# Torent_Module.net
KiCad netlist of a schematic drawn in EAGLE
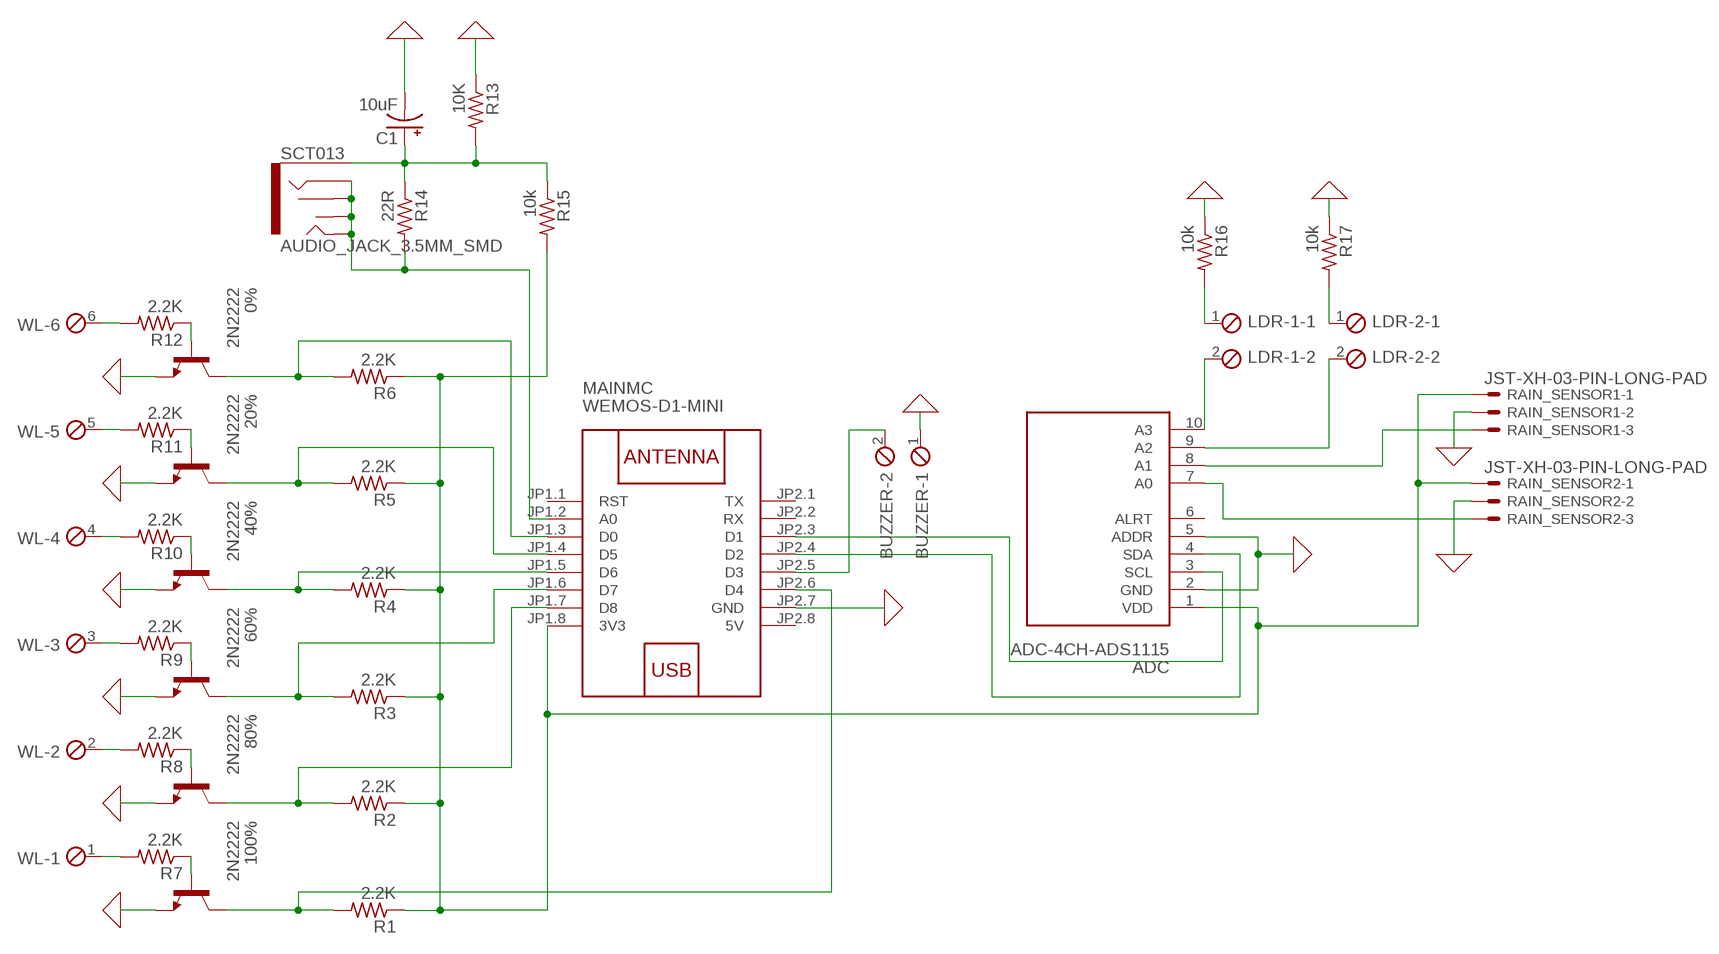
[diagram p0: schematic, sheet 1]

(export (version "E")
  (design (tool "Eeschema 10.0.6"))
  (components
    (comp (ref "0%")
      (value "2N2222")
      (footprint "eagle-import:TO92-EBC-OVAL")
      (libsource (lib "eagle-import") (part "2N2222"))
    )
    (comp (ref "20%")
      (value "2N2222")
      (footprint "eagle-import:TO92-EBC-OVAL")
      (libsource (lib "eagle-import") (part "2N2222"))
    )
    (comp (ref "40%")
      (value "2N2222")
      (footprint "eagle-import:TO92-EBC-OVAL")
      (libsource (lib "eagle-import") (part "2N2222"))
    )
    (comp (ref "60%")
      (value "2N2222")
      (footprint "eagle-import:TO92-EBC-OVAL")
      (libsource (lib "eagle-import") (part "2N2222"))
    )
    (comp (ref "80%")
      (value "2N2222")
      (footprint "eagle-import:TO92-EBC-OVAL")
      (libsource (lib "eagle-import") (part "2N2222"))
    )
    (comp (ref "100%")
      (value "2N2222")
      (footprint "eagle-import:TO92-EBC-OVAL")
      (libsource (lib "eagle-import") (part "2N2222"))
    )
    (comp (ref "ADC")
      (value "ADC-4CH-ADS1115")
      (footprint "eagle-import:ADC-4CH-ADS1115")
      (libsource (lib "eagle-import") (part "ADC-4CH-ADS1115"))
    )
    (comp (ref "BUZZER")
      (value "MPT2")
      (footprint "eagle-import:2POL254")
      (libsource (lib "eagle-import") (part "MPT2"))
    )
    (comp (ref "C1")
      (value "10uF")
      (footprint "eagle-import:TT2D7")
      (libsource (lib "eagle-import") (part "CPOL-USTT2D7"))
    )
    (comp (ref "LDR-1")
      (value "MPT2")
      (footprint "eagle-import:2POL254")
      (libsource (lib "eagle-import") (part "MPT2"))
    )
    (comp (ref "LDR-2")
      (value "MPT2")
      (footprint "eagle-import:2POL254")
      (libsource (lib "eagle-import") (part "MPT2"))
    )
    (comp (ref "MAINMC")
      (value "WEMOS-D1-MINI")
      (footprint "eagle-import:WEMOS-D1-MINI")
      (libsource (lib "eagle-import") (part "WEMOS-D1-MINI"))
    )
    (comp (ref "R1")
      (value "2.2K")
      (footprint "eagle-import:0207_9")
      (libsource (lib "eagle-import") (part "R-US_0207/9"))
    )
    (comp (ref "R2")
      (value "2.2K")
      (footprint "eagle-import:0207_9")
      (libsource (lib "eagle-import") (part "R-US_0207/9"))
    )
    (comp (ref "R3")
      (value "2.2K")
      (footprint "eagle-import:0207_9")
      (libsource (lib "eagle-import") (part "R-US_0207/9"))
    )
    (comp (ref "R4")
      (value "2.2K")
      (footprint "eagle-import:0207_9")
      (libsource (lib "eagle-import") (part "R-US_0207/9"))
    )
    (comp (ref "R5")
      (value "2.2K")
      (footprint "eagle-import:0207_9")
      (libsource (lib "eagle-import") (part "R-US_0207/9"))
    )
    (comp (ref "R6")
      (value "2.2K")
      (footprint "eagle-import:0207_9")
      (libsource (lib "eagle-import") (part "R-US_0207/9"))
    )
    (comp (ref "R7")
      (value "2.2K")
      (footprint "eagle-import:0207_9")
      (libsource (lib "eagle-import") (part "R-US_0207/9"))
    )
    (comp (ref "R8")
      (value "2.2K")
      (footprint "eagle-import:0207_9")
      (libsource (lib "eagle-import") (part "R-US_0207/9"))
    )
    (comp (ref "R9")
      (value "2.2K")
      (footprint "eagle-import:0207_9")
      (libsource (lib "eagle-import") (part "R-US_0207/9"))
    )
    (comp (ref "R10")
      (value "2.2K")
      (footprint "eagle-import:0207_9")
      (libsource (lib "eagle-import") (part "R-US_0207/9"))
    )
    (comp (ref "R11")
      (value "2.2K")
      (footprint "eagle-import:0207_9")
      (libsource (lib "eagle-import") (part "R-US_0207/9"))
    )
    (comp (ref "R12")
      (value "2.2K")
      (footprint "eagle-import:0207_9")
      (libsource (lib "eagle-import") (part "R-US_0207/9"))
    )
    (comp (ref "R13")
      (value "10K")
      (footprint "eagle-import:0207_9")
      (libsource (lib "eagle-import") (part "R-US_0207/9"))
    )
    (comp (ref "R14")
      (value "22R")
      (footprint "eagle-import:0207_9")
      (libsource (lib "eagle-import") (part "R-US_0207/9"))
    )
    (comp (ref "R15")
      (value "10k")
      (footprint "eagle-import:0207_9")
      (libsource (lib "eagle-import") (part "R-US_0207/9"))
    )
    (comp (ref "R16")
      (value "10k")
      (footprint "eagle-import:0207_9")
      (libsource (lib "eagle-import") (part "R-US_0207/9"))
    )
    (comp (ref "R17")
      (value "10k")
      (footprint "eagle-import:0207_9")
      (libsource (lib "eagle-import") (part "R-US_0207/9"))
    )
    (comp (ref "RAIN_SENSOR1")
      (value "JST-XH-03-PIN-LONG-PAD")
      (footprint "eagle-import:JST-XH-03-PACKAGE-LONG-PAD")
      (libsource (lib "eagle-import") (part "JST-XH-03-PIN-LONG-PAD"))
    )
    (comp (ref "RAIN_SENSOR2")
      (value "JST-XH-03-PIN-LONG-PAD")
      (footprint "eagle-import:JST-XH-03-PACKAGE-LONG-PAD")
      (libsource (lib "eagle-import") (part "JST-XH-03-PIN-LONG-PAD"))
    )
    (comp (ref "SCT013")
      (value "AUDIO_JACK_3.5MM_SMD")
      (footprint "eagle-import:AUDIO-JACK-3.5MM-SMD")
      (libsource (lib "eagle-import") (part "AUDIO_JACK_3.5MM_SMD"))
    )
    (comp (ref "WL")
      (value "MPT6")
      (footprint "eagle-import:6POL254")
      (libsource (lib "eagle-import") (part "MPT6"))
    )
  )
  (nets
    (net (code "1") (name "/5V") (class "Default")
      (node (ref "MAINMC") (pin "JP2.8") (pinfunction "5V_JP2.8") (pintype "power_in"))
    )
    (net (code "2") (name "GND") (class "Default")
      (node (ref "0%") (pin "E") (pinfunction "E_E") (pintype "passive"))
      (node (ref "100%") (pin "E") (pinfunction "E_E") (pintype "passive"))
      (node (ref "20%") (pin "E") (pinfunction "E_E") (pintype "passive"))
      (node (ref "40%") (pin "E") (pinfunction "E_E") (pintype "passive"))
      (node (ref "60%") (pin "E") (pinfunction "E_E") (pintype "passive"))
      (node (ref "80%") (pin "E") (pinfunction "E_E") (pintype "passive"))
      (node (ref "ADC") (pin "2") (pinfunction "GND_2") (pintype "power_in"))
      (node (ref "ADC") (pin "5") (pinfunction "ADDR_5") (pintype "bidirectional"))
      (node (ref "BUZZER") (pin "1") (pinfunction "1_1") (pintype "passive"))
      (node (ref "C1") (pin "-") (pinfunction "-_-") (pintype "passive"))
      (node (ref "MAINMC") (pin "JP2.7") (pinfunction "GND_JP2.7") (pintype "power_in"))
      (node (ref "R13") (pin "1") (pinfunction "1_1") (pintype "passive"))
      (node (ref "R16") (pin "1") (pinfunction "1_1") (pintype "passive"))
      (node (ref "R17") (pin "1") (pinfunction "1_1") (pintype "passive"))
      (node (ref "RAIN_SENSOR1") (pin "2") (pinfunction "S_2") (pintype "passive"))
      (node (ref "RAIN_SENSOR2") (pin "2") (pinfunction "S_2") (pintype "passive"))
    )
    (net (code "3") (name "Net-(0%-PadB)") (class "Default")
      (node (ref "0%") (pin "B") (pinfunction "B_B") (pintype "passive"))
      (node (ref "R12") (pin "1") (pinfunction "1_1") (pintype "passive"))
    )
    (net (code "4") (name "Net-(20%-PadB)") (class "Default")
      (node (ref "20%") (pin "B") (pinfunction "B_B") (pintype "passive"))
      (node (ref "R11") (pin "1") (pinfunction "1_1") (pintype "passive"))
    )
    (net (code "5") (name "Net-(40%-PadB)") (class "Default")
      (node (ref "40%") (pin "B") (pinfunction "B_B") (pintype "passive"))
      (node (ref "R10") (pin "1") (pinfunction "1_1") (pintype "passive"))
    )
    (net (code "6") (name "Net-(60%-PadB)") (class "Default")
      (node (ref "60%") (pin "B") (pinfunction "B_B") (pintype "passive"))
      (node (ref "R9") (pin "1") (pinfunction "1_1") (pintype "passive"))
    )
    (net (code "7") (name "Net-(80%-PadB)") (class "Default")
      (node (ref "80%") (pin "B") (pinfunction "B_B") (pintype "passive"))
      (node (ref "R8") (pin "1") (pinfunction "1_1") (pintype "passive"))
    )
    (net (code "8") (name "Net-(100%-PadB)") (class "Default")
      (node (ref "100%") (pin "B") (pinfunction "B_B") (pintype "passive"))
      (node (ref "R7") (pin "1") (pinfunction "1_1") (pintype "passive"))
    )
    (net (code "9") (name "Net-(ADC-A0)") (class "Default")
      (node (ref "ADC") (pin "7") (pinfunction "A0_7") (pintype "input"))
      (node (ref "RAIN_SENSOR2") (pin "3") (pinfunction "S_3") (pintype "passive"))
    )
    (net (code "10") (name "Net-(ADC-A1)") (class "Default")
      (node (ref "ADC") (pin "8") (pinfunction "A1_8") (pintype "input"))
      (node (ref "RAIN_SENSOR1") (pin "3") (pinfunction "S_3") (pintype "passive"))
    )
    (net (code "11") (name "Net-(ADC-A2)") (class "Default")
      (node (ref "ADC") (pin "9") (pinfunction "A2_9") (pintype "input"))
      (node (ref "LDR-2") (pin "2") (pinfunction "1_2") (pintype "passive"))
    )
    (net (code "12") (name "Net-(ADC-A3)") (class "Default")
      (node (ref "ADC") (pin "10") (pinfunction "A3_10") (pintype "input"))
      (node (ref "LDR-1") (pin "2") (pinfunction "1_2") (pintype "passive"))
    )
    (net (code "13") (name "Net-(ADC-SCL)") (class "Default")
      (node (ref "ADC") (pin "3") (pinfunction "SCL_3") (pintype "bidirectional"))
      (node (ref "MAINMC") (pin "JP2.3") (pinfunction "D1_JP2.3") (pintype "bidirectional"))
    )
    (net (code "14") (name "Net-(ADC-SDA)") (class "Default")
      (node (ref "ADC") (pin "4") (pinfunction "SDA_4") (pintype "bidirectional"))
      (node (ref "MAINMC") (pin "JP2.4") (pinfunction "D2_JP2.4") (pintype "bidirectional"))
    )
    (net (code "15") (name "Net-(ADC-VDD)") (class "Default")
      (node (ref "ADC") (pin "1") (pinfunction "VDD_1") (pintype "power_in"))
      (node (ref "MAINMC") (pin "JP1.8") (pinfunction "3V3_JP1.8") (pintype "power_in"))
      (node (ref "R1") (pin "1") (pinfunction "1_1") (pintype "passive"))
      (node (ref "R15") (pin "2") (pinfunction "2_2") (pintype "passive"))
      (node (ref "R2") (pin "1") (pinfunction "1_1") (pintype "passive"))
      (node (ref "R3") (pin "1") (pinfunction "1_1") (pintype "passive"))
      (node (ref "R4") (pin "1") (pinfunction "1_1") (pintype "passive"))
      (node (ref "R5") (pin "1") (pinfunction "1_1") (pintype "passive"))
      (node (ref "R6") (pin "1") (pinfunction "1_1") (pintype "passive"))
      (node (ref "RAIN_SENSOR1") (pin "1") (pinfunction "S_1") (pintype "passive"))
      (node (ref "RAIN_SENSOR2") (pin "1") (pinfunction "S_1") (pintype "passive"))
    )
    (net (code "16") (name "Net-(BUZZERB-1)") (class "Default")
      (node (ref "BUZZER") (pin "2") (pinfunction "1_2") (pintype "passive"))
      (node (ref "MAINMC") (pin "JP2.5") (pinfunction "D3_JP2.5") (pintype "bidirectional"))
    )
    (net (code "17") (name "Net-(C1-Pad+)") (class "Default")
      (node (ref "C1") (pin "+") (pinfunction "+_+") (pintype "passive"))
      (node (ref "R13") (pin "2") (pinfunction "2_2") (pintype "passive"))
      (node (ref "R14") (pin "1") (pinfunction "1_1") (pintype "passive"))
      (node (ref "R15") (pin "1") (pinfunction "1_1") (pintype "passive"))
      (node (ref "SCT013") (pin "SLEEVE") (pinfunction "SLEEVE_SLEEVE") (pintype "bidirectional"))
    )
    (net (code "18") (name "Net-(LDR-1-Pad1)") (class "Default")
      (node (ref "LDR-1") (pin "1") (pinfunction "1_1") (pintype "passive"))
      (node (ref "R16") (pin "2") (pinfunction "2_2") (pintype "passive"))
    )
    (net (code "19") (name "Net-(LDR-2-Pad1)") (class "Default")
      (node (ref "LDR-2") (pin "1") (pinfunction "1_1") (pintype "passive"))
      (node (ref "R17") (pin "2") (pinfunction "2_2") (pintype "passive"))
    )
    (net (code "20") (name "Net-(MAINMC-A0)") (class "Default")
      (node (ref "MAINMC") (pin "JP1.2") (pinfunction "A0_JP1.2") (pintype "bidirectional"))
      (node (ref "R14") (pin "2") (pinfunction "2_2") (pintype "passive"))
      (node (ref "SCT013") (pin "RING") (pinfunction "RING_RING") (pintype "bidirectional"))
      (node (ref "SCT013") (pin "RSH") (pinfunction "RSH_RSH") (pintype "bidirectional"))
      (node (ref "SCT013") (pin "TIP") (pinfunction "TIP_TIP") (pintype "bidirectional"))
      (node (ref "SCT013") (pin "TSH") (pinfunction "TSH_TSH") (pintype "bidirectional"))
    )
    (net (code "21") (name "Net-(MAINMC-D0)") (class "Default")
      (node (ref "0%") (pin "C") (pinfunction "C_C") (pintype "passive"))
      (node (ref "MAINMC") (pin "JP1.3") (pinfunction "D0_JP1.3") (pintype "bidirectional"))
      (node (ref "R6") (pin "2") (pinfunction "2_2") (pintype "passive"))
    )
    (net (code "22") (name "Net-(MAINMC-D4)") (class "Default")
      (node (ref "100%") (pin "C") (pinfunction "C_C") (pintype "passive"))
      (node (ref "MAINMC") (pin "JP2.6") (pinfunction "D4_JP2.6") (pintype "bidirectional"))
      (node (ref "R1") (pin "2") (pinfunction "2_2") (pintype "passive"))
    )
    (net (code "23") (name "Net-(MAINMC-D5)") (class "Default")
      (node (ref "20%") (pin "C") (pinfunction "C_C") (pintype "passive"))
      (node (ref "MAINMC") (pin "JP1.4") (pinfunction "D5_JP1.4") (pintype "bidirectional"))
      (node (ref "R5") (pin "2") (pinfunction "2_2") (pintype "passive"))
    )
    (net (code "24") (name "Net-(MAINMC-D6)") (class "Default")
      (node (ref "40%") (pin "C") (pinfunction "C_C") (pintype "passive"))
      (node (ref "MAINMC") (pin "JP1.5") (pinfunction "D6_JP1.5") (pintype "bidirectional"))
      (node (ref "R4") (pin "2") (pinfunction "2_2") (pintype "passive"))
    )
    (net (code "25") (name "Net-(MAINMC-D7)") (class "Default")
      (node (ref "60%") (pin "C") (pinfunction "C_C") (pintype "passive"))
      (node (ref "MAINMC") (pin "JP1.6") (pinfunction "D7_JP1.6") (pintype "bidirectional"))
      (node (ref "R3") (pin "2") (pinfunction "2_2") (pintype "passive"))
    )
    (net (code "26") (name "Net-(MAINMC-D8)") (class "Default")
      (node (ref "80%") (pin "C") (pinfunction "C_C") (pintype "passive"))
      (node (ref "MAINMC") (pin "JP1.7") (pinfunction "D8_JP1.7") (pintype "bidirectional"))
      (node (ref "R2") (pin "2") (pinfunction "2_2") (pintype "passive"))
    )
    (net (code "27") (name "Net-(R7-Pad2)") (class "Default")
      (node (ref "R7") (pin "2") (pinfunction "2_2") (pintype "passive"))
      (node (ref "WL") (pin "1") (pinfunction "1_1") (pintype "passive"))
    )
    (net (code "28") (name "Net-(WLB-1)") (class "Default")
      (node (ref "R8") (pin "2") (pinfunction "2_2") (pintype "passive"))
      (node (ref "WL") (pin "2") (pinfunction "1_2") (pintype "passive"))
    )
    (net (code "29") (name "Net-(WLC-1)") (class "Default")
      (node (ref "R9") (pin "2") (pinfunction "2_2") (pintype "passive"))
      (node (ref "WL") (pin "3") (pinfunction "1_3") (pintype "passive"))
    )
    (net (code "30") (name "Net-(WLD-1)") (class "Default")
      (node (ref "R10") (pin "2") (pinfunction "2_2") (pintype "passive"))
      (node (ref "WL") (pin "4") (pinfunction "1_4") (pintype "passive"))
    )
    (net (code "31") (name "Net-(WLE-1)") (class "Default")
      (node (ref "R11") (pin "2") (pinfunction "2_2") (pintype "passive"))
      (node (ref "WL") (pin "5") (pinfunction "1_5") (pintype "passive"))
    )
    (net (code "32") (name "Net-(WLF-1)") (class "Default")
      (node (ref "R12") (pin "2") (pinfunction "2_2") (pintype "passive"))
      (node (ref "WL") (pin "6") (pinfunction "1_6") (pintype "passive"))
    )
    (net (code "33") (name "unconnected-(ADC-ALRT-Pad6)") (class "Default")
      (node (ref "ADC") (pin "6") (pinfunction "ALRT_6") (pintype "bidirectional"))
    )
    (net (code "34") (name "unconnected-(MAINMC-RST-PadJP1.1)") (class "Default")
      (node (ref "MAINMC") (pin "JP1.1") (pinfunction "RST_JP1.1") (pintype "bidirectional"))
    )
    (net (code "35") (name "unconnected-(MAINMC-RX-PadJP2.2)") (class "Default")
      (node (ref "MAINMC") (pin "JP2.2") (pinfunction "RX_JP2.2") (pintype "bidirectional"))
    )
    (net (code "36") (name "unconnected-(MAINMC-TX-PadJP2.1)") (class "Default")
      (node (ref "MAINMC") (pin "JP2.1") (pinfunction "TX_JP2.1") (pintype "bidirectional"))
    )
  )
)
